# Data_IO.net
KiCad netlist of a schematic drawn in Altium Designer
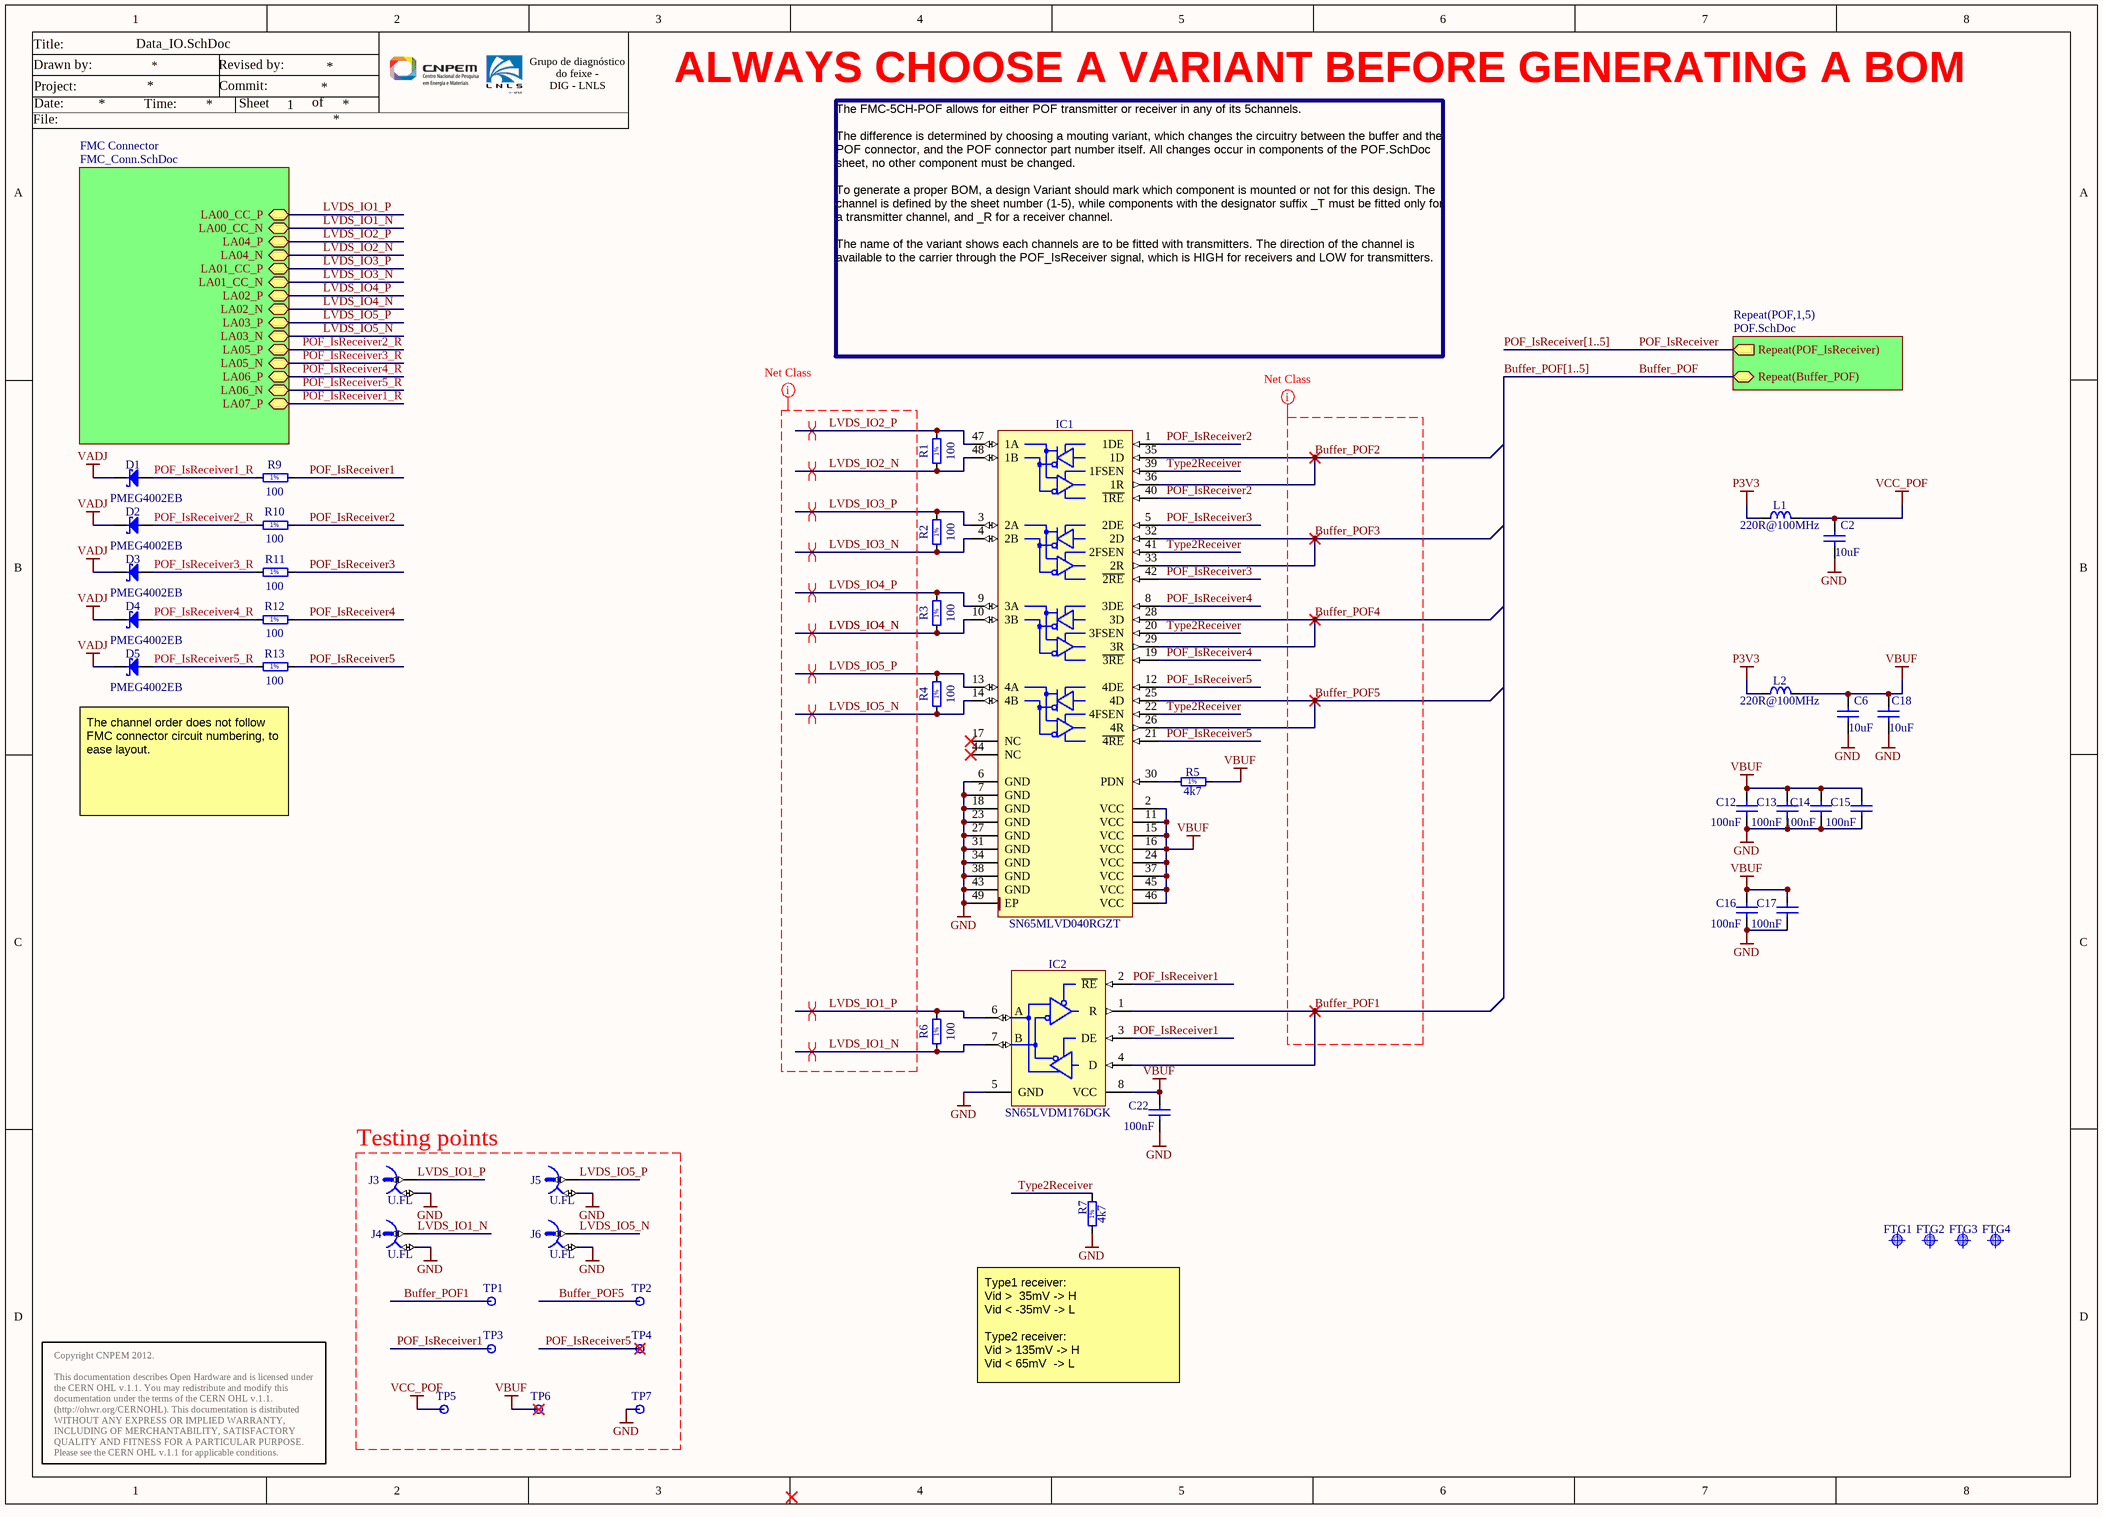
[diagram p0: Data_IO.SchDoc]

(export (version "E")
  (design (tool "Eeschema 10.0.6"))
  (components
    (comp (ref "C2")
      (value "10uF")
      (footprint "CAPC2012X135N")
      (description "Non-polarised capacitor")
      (fields
        (field (name "PART NUMBER") "CC0805_10UF_10V_10%_X7R")
        (field (name "VOLTAGE") "10V")
        (field (name "AUTHOR") "CERN DEM JLC")
      )
      (libsource (lib "Capacitors") (part "Capacitor - non polarized"))
    )
    (comp (ref "C6")
      (value "10uF")
      (footprint "CAPC2012X135N")
      (description "Non-polarised capacitor")
      (fields
        (field (name "PART NUMBER") "CC0805_10UF_10V_10%_X7R")
        (field (name "VOLTAGE") "10V")
        (field (name "AUTHOR") "CERN DEM JLC")
      )
      (libsource (lib "Capacitors") (part "Capacitor - non polarized"))
    )
    (comp (ref "C12")
      (value "100nF")
      (footprint "CAPC1005X55N")
      (description "Non-polarised capacitor")
      (fields
        (field (name "PART NUMBER") "CC0402_100NF_16V_10%_X5R")
        (field (name "VOLTAGE") "16V")
        (field (name "AUTHOR") "CERN DEM JLC")
      )
      (libsource (lib "Capacitors") (part "Capacitor - non polarized"))
    )
    (comp (ref "C13")
      (value "100nF")
      (footprint "CAPC1005X55N")
      (description "Non-polarised capacitor")
      (fields
        (field (name "PART NUMBER") "CC0402_100NF_16V_10%_X5R")
        (field (name "VOLTAGE") "16V")
        (field (name "AUTHOR") "CERN DEM JLC")
      )
      (libsource (lib "Capacitors") (part "Capacitor - non polarized"))
    )
    (comp (ref "C14")
      (value "100nF")
      (footprint "CAPC1005X55N")
      (description "Non-polarised capacitor")
      (fields
        (field (name "PART NUMBER") "CC0402_100NF_16V_10%_X5R")
        (field (name "VOLTAGE") "16V")
        (field (name "AUTHOR") "CERN DEM JLC")
      )
      (libsource (lib "Capacitors") (part "Capacitor - non polarized"))
    )
    (comp (ref "C15")
      (value "100nF")
      (footprint "CAPC1005X55N")
      (description "Non-polarised capacitor")
      (fields
        (field (name "PART NUMBER") "CC0402_100NF_16V_10%_X5R")
        (field (name "VOLTAGE") "16V")
        (field (name "AUTHOR") "CERN DEM JLC")
      )
      (libsource (lib "Capacitors") (part "Capacitor - non polarized"))
    )
    (comp (ref "C16")
      (value "100nF")
      (footprint "CAPC1005X55N")
      (description "Non-polarised capacitor")
      (fields
        (field (name "PART NUMBER") "CC0402_100NF_16V_10%_X5R")
        (field (name "VOLTAGE") "16V")
        (field (name "AUTHOR") "CERN DEM JLC")
      )
      (libsource (lib "Capacitors") (part "Capacitor - non polarized"))
    )
    (comp (ref "C17")
      (value "100nF")
      (footprint "CAPC1005X55N")
      (description "Non-polarised capacitor")
      (fields
        (field (name "PART NUMBER") "CC0402_100NF_16V_10%_X5R")
        (field (name "VOLTAGE") "16V")
        (field (name "AUTHOR") "CERN DEM JLC")
      )
      (libsource (lib "Capacitors") (part "Capacitor - non polarized"))
    )
    (comp (ref "C18")
      (value "10uF")
      (footprint "CAPC2012X135N")
      (description "Non-polarised capacitor")
      (fields
        (field (name "PART NUMBER") "CC0805_10UF_10V_10%_X7R")
        (field (name "VOLTAGE") "10V")
        (field (name "AUTHOR") "CERN DEM JLC")
      )
      (libsource (lib "Capacitors") (part "Capacitor - non polarized"))
    )
    (comp (ref "C22")
      (value "100nF")
      (footprint "CAPC1005X55N")
      (description "Non-polarised capacitor")
      (fields
        (field (name "PART NUMBER") "CC0402_100NF_16V_10%_X5R")
        (field (name "VOLTAGE") "16V")
        (field (name "AUTHOR") "CERN DEM JLC")
      )
      (libsource (lib "Capacitors") (part "Capacitor - non polarized"))
    )
    (comp (ref "D1")
      (value "PMEG4002EB")
      (footprint "SODFL1608X65N")
      (description "Schottky Diode")
      (fields
        (field (name "VOLTAGE") "40V")
        (field (name "POWER") "200mA")
        (field (name "AUTHOR") "CERN DEM JMW")
      )
      (libsource (lib "ICs And Semiconductors") (part "Diode Schottky"))
    )
    (comp (ref "D2")
      (value "PMEG4002EB")
      (footprint "SODFL1608X65N")
      (description "Schottky Diode")
      (fields
        (field (name "VOLTAGE") "40V")
        (field (name "POWER") "200mA")
        (field (name "AUTHOR") "CERN DEM JMW")
      )
      (libsource (lib "ICs And Semiconductors") (part "Diode Schottky"))
    )
    (comp (ref "D3")
      (value "PMEG4002EB")
      (footprint "SODFL1608X65N")
      (description "Schottky Diode")
      (fields
        (field (name "VOLTAGE") "40V")
        (field (name "POWER") "200mA")
        (field (name "AUTHOR") "CERN DEM JMW")
      )
      (libsource (lib "ICs And Semiconductors") (part "Diode Schottky"))
    )
    (comp (ref "D4")
      (value "PMEG4002EB")
      (footprint "SODFL1608X65N")
      (description "Schottky Diode")
      (fields
        (field (name "VOLTAGE") "40V")
        (field (name "POWER") "200mA")
        (field (name "AUTHOR") "CERN DEM JMW")
      )
      (libsource (lib "ICs And Semiconductors") (part "Diode Schottky"))
    )
    (comp (ref "D5")
      (value "PMEG4002EB")
      (footprint "SODFL1608X65N")
      (description "Schottky Diode")
      (fields
        (field (name "VOLTAGE") "40V")
        (field (name "POWER") "200mA")
        (field (name "AUTHOR") "CERN DEM JMW")
      )
      (libsource (lib "ICs And Semiconductors") (part "Diode Schottky"))
    )
    (comp (ref "FTG1")
      (value "Use only in PCB")
      (footprint "FIDUCIAL_TOP_S100-200")
      (description "Fiducial Target")
      (fields (field (name "PART NUMBER") "FIDUCIAL_TARGET_S100-200") (field (name "AUTHOR") "CERN DEM JLC"))
      (libsource (lib "Eletro-mechanical") (part "Fiducial Target"))
    )
    (comp (ref "FTG2")
      (value "Use only in PCB")
      (footprint "FIDUCIAL_TOP_S100-200")
      (description "Fiducial Target")
      (fields (field (name "PART NUMBER") "FIDUCIAL_TARGET_S100-200") (field (name "AUTHOR") "CERN DEM JLC"))
      (libsource (lib "Eletro-mechanical") (part "Fiducial Target"))
    )
    (comp (ref "FTG3")
      (value "Use only in PCB")
      (footprint "FIDUCIAL_TOP_S100-200")
      (description "Fiducial Target")
      (fields (field (name "PART NUMBER") "FIDUCIAL_TARGET_S100-200") (field (name "AUTHOR") "CERN DEM JLC"))
      (libsource (lib "Eletro-mechanical") (part "Fiducial Target"))
    )
    (comp (ref "FTG4")
      (value "Use only in PCB")
      (footprint "FIDUCIAL_TOP_S100-200")
      (description "Fiducial Target")
      (fields (field (name "PART NUMBER") "FIDUCIAL_TARGET_S100-200") (field (name "AUTHOR") "CERN DEM JLC"))
      (libsource (lib "Eletro-mechanical") (part "Fiducial Target"))
    )
    (comp (ref "IC1")
      (value "SN65MLVD040RGZT")
      (footprint "QFN50P700X700X100-49N-S420")
      (description "4-Channel Half-Duplex M-LVDS Line Transceiver")
      (fields (field (name "MANUFACTURER") "TEXAS INSTRUMENTS") (field (name "AUTHOR") "CERN DEM JLC"))
      (libsource (lib "ICs And Semiconductors") (part "SN65MLVD040"))
    )
    (comp (ref "IC2")
      (value "SN65LVDM176DGK")
      (footprint "SOP65P490X110-8N")
      (description "Half-Duplex LVDM Transceiver")
      (fields (field (name "MANUFACTURER") "TEXAS INSTRUMENTS") (field (name "AUTHOR") "CERN DEM JLC"))
      (libsource (lib "ICs And Semiconductors") (part "SN65LVDM176"))
    )
    (comp (ref "J3")
      (value "U.FL")
      (footprint "HIROSE_U.FL-R-SMT-1(10)")
      (fields
        (field (name "PART NUMBER") "HIROSE_U.FL-R-SMT-1(10)")
        (field (name "MANUFACTURER") "HIROSE (HRS)")
        (field (name "MANUFACTURER PART NUMBER") "U.FL-R-SMT-1(10)")
        (field (name "AUTHOR") "CERN DEM JLC")
      )
      (libsource (lib "Connectors") (part "Coax_1Male_1Shield"))
    )
    (comp (ref "J4")
      (value "U.FL")
      (footprint "HIROSE_U.FL-R-SMT-1(10)")
      (fields
        (field (name "PART NUMBER") "HIROSE_U.FL-R-SMT-1(10)")
        (field (name "MANUFACTURER") "HIROSE (HRS)")
        (field (name "MANUFACTURER PART NUMBER") "U.FL-R-SMT-1(10)")
        (field (name "AUTHOR") "CERN DEM JLC")
      )
      (libsource (lib "Connectors") (part "Coax_1Male_1Shield"))
    )
    (comp (ref "J5")
      (value "U.FL")
      (footprint "HIROSE_U.FL-R-SMT-1(10)")
      (fields
        (field (name "PART NUMBER") "HIROSE_U.FL-R-SMT-1(10)")
        (field (name "MANUFACTURER") "HIROSE (HRS)")
        (field (name "MANUFACTURER PART NUMBER") "U.FL-R-SMT-1(10)")
        (field (name "AUTHOR") "CERN DEM JLC")
      )
      (libsource (lib "Connectors") (part "Coax_1Male_1Shield"))
    )
    (comp (ref "J6")
      (value "U.FL")
      (footprint "HIROSE_U.FL-R-SMT-1(10)")
      (fields
        (field (name "PART NUMBER") "HIROSE_U.FL-R-SMT-1(10)")
        (field (name "MANUFACTURER") "HIROSE (HRS)")
        (field (name "MANUFACTURER PART NUMBER") "U.FL-R-SMT-1(10)")
        (field (name "AUTHOR") "CERN DEM JLC")
      )
      (libsource (lib "Connectors") (part "Coax_1Male_1Shield"))
    )
    (comp (ref "L1")
      (value "220R@100MHz")
      (footprint "INDC2012X105N")
      (description "Inductor")
      (fields
        (field (name "PART NUMBER") "IND0805_MURATA_BLM21PG221SN1D")
        (field (name "POWER") "2A")
        (field (name "AUTHOR") "CERN DEM JLC")
      )
      (libsource (lib "Inductors & Transformers") (part "Inductor"))
    )
    (comp (ref "L2")
      (value "220R@100MHz")
      (footprint "INDC2012X105N")
      (description "Inductor")
      (fields
        (field (name "PART NUMBER") "IND0805_MURATA_BLM21PG221SN1D")
        (field (name "POWER") "2A")
        (field (name "AUTHOR") "CERN DEM JLC")
      )
      (libsource (lib "Inductors & Transformers") (part "Inductor"))
    )
    (comp (ref "R1")
      (value "100")
      (footprint "RESC1005X40N")
      (description "Resistor - 1%")
      (fields
        (field (name "PART NUMBER") "R0402_100R_1%_0.0625W_100PPM")
        (field (name "POWER") "0.0625W")
        (field (name "AUTHOR") "CERN DEM JLC")
      )
      (libsource (lib "Resistors") (part "Resistor - 1%"))
    )
    (comp (ref "R2")
      (value "100")
      (footprint "RESC1005X40N")
      (description "Resistor - 1%")
      (fields
        (field (name "PART NUMBER") "R0402_100R_1%_0.0625W_100PPM")
        (field (name "POWER") "0.0625W")
        (field (name "AUTHOR") "CERN DEM JLC")
      )
      (libsource (lib "Resistors") (part "Resistor - 1%"))
    )
    (comp (ref "R3")
      (value "100")
      (footprint "RESC1005X40N")
      (description "Resistor - 1%")
      (fields
        (field (name "PART NUMBER") "R0402_100R_1%_0.0625W_100PPM")
        (field (name "POWER") "0.0625W")
        (field (name "AUTHOR") "CERN DEM JLC")
      )
      (libsource (lib "Resistors") (part "Resistor - 1%"))
    )
    (comp (ref "R4")
      (value "100")
      (footprint "RESC1005X40N")
      (description "Resistor - 1%")
      (fields
        (field (name "PART NUMBER") "R0402_100R_1%_0.0625W_100PPM")
        (field (name "POWER") "0.0625W")
        (field (name "AUTHOR") "CERN DEM JLC")
      )
      (libsource (lib "Resistors") (part "Resistor - 1%"))
    )
    (comp (ref "R5")
      (value "4k7")
      (footprint "RESC1005X40N")
      (description "Resistor - 1%")
      (fields
        (field (name "PART NUMBER") "R0402_4K7_1%_0.0625W_100PPM")
        (field (name "POWER") "0.0625W")
        (field (name "AUTHOR") "CERN DEM JLC")
      )
      (libsource (lib "Resistors") (part "Resistor - 1%"))
    )
    (comp (ref "R6")
      (value "100")
      (footprint "RESC1005X40N")
      (description "Resistor - 1%")
      (fields
        (field (name "PART NUMBER") "R0402_100R_1%_0.0625W_100PPM")
        (field (name "POWER") "0.0625W")
        (field (name "AUTHOR") "CERN DEM JLC")
      )
      (libsource (lib "Resistors") (part "Resistor - 1%"))
    )
    (comp (ref "R7")
      (value "4k7")
      (footprint "RESC1005X40N")
      (description "Resistor - 1%")
      (fields
        (field (name "PART NUMBER") "R0402_4K7_1%_0.0625W_100PPM")
        (field (name "POWER") "0.0625W")
        (field (name "AUTHOR") "CERN DEM JLC")
      )
      (libsource (lib "Resistors") (part "Resistor - 1%"))
    )
    (comp (ref "R9")
      (value "100")
      (footprint "RESC1005X40N")
      (description "Resistor - 1%")
      (fields
        (field (name "PART NUMBER") "R0402_100R_1%_0.0625W_100PPM")
        (field (name "POWER") "0.0625W")
        (field (name "AUTHOR") "CERN DEM JLC")
      )
      (libsource (lib "Resistors") (part "Resistor - 1%"))
    )
    (comp (ref "R10")
      (value "100")
      (footprint "RESC1005X40N")
      (description "Resistor - 1%")
      (fields
        (field (name "PART NUMBER") "R0402_100R_1%_0.0625W_100PPM")
        (field (name "POWER") "0.0625W")
        (field (name "AUTHOR") "CERN DEM JLC")
      )
      (libsource (lib "Resistors") (part "Resistor - 1%"))
    )
    (comp (ref "R11")
      (value "100")
      (footprint "RESC1005X40N")
      (description "Resistor - 1%")
      (fields
        (field (name "PART NUMBER") "R0402_100R_1%_0.0625W_100PPM")
        (field (name "POWER") "0.0625W")
        (field (name "AUTHOR") "CERN DEM JLC")
      )
      (libsource (lib "Resistors") (part "Resistor - 1%"))
    )
    (comp (ref "R12")
      (value "100")
      (footprint "RESC1005X40N")
      (description "Resistor - 1%")
      (fields
        (field (name "PART NUMBER") "R0402_100R_1%_0.0625W_100PPM")
        (field (name "POWER") "0.0625W")
        (field (name "AUTHOR") "CERN DEM JLC")
      )
      (libsource (lib "Resistors") (part "Resistor - 1%"))
    )
    (comp (ref "R13")
      (value "100")
      (footprint "RESC1005X40N")
      (description "Resistor - 1%")
      (fields
        (field (name "PART NUMBER") "R0402_100R_1%_0.0625W_100PPM")
        (field (name "POWER") "0.0625W")
        (field (name "AUTHOR") "CERN DEM JLC")
      )
      (libsource (lib "Resistors") (part "Resistor - 1%"))
    )
    (comp (ref "TP1")
      (value "Plated Hole")
      (footprint "c300h160")
      (description "Single Terminal Socket")
      (fields (field (name "PART NUMBER") "PLATED_HOLE1.6_PAD3.0") (field (name "AUTHOR") "CERN DEM JMW"))
      (libsource (lib "Eletro-mechanical") (part "Single Terminal Socket"))
    )
    (comp (ref "TP2")
      (value "Plated Hole")
      (footprint "c300h160")
      (description "Single Terminal Socket")
      (fields (field (name "PART NUMBER") "PLATED_HOLE1.6_PAD3.0") (field (name "AUTHOR") "CERN DEM JMW"))
      (libsource (lib "Eletro-mechanical") (part "Single Terminal Socket"))
    )
    (comp (ref "TP3")
      (value "Plated Hole")
      (footprint "c300h160")
      (description "Single Terminal Socket")
      (fields (field (name "PART NUMBER") "PLATED_HOLE1.6_PAD3.0") (field (name "AUTHOR") "CERN DEM JMW"))
      (libsource (lib "Eletro-mechanical") (part "Single Terminal Socket"))
    )
    (comp (ref "TP4")
      (value "Plated Hole")
      (footprint "c300h160")
      (description "Single Terminal Socket")
      (fields (field (name "PART NUMBER") "PLATED_HOLE1.6_PAD3.0") (field (name "AUTHOR") "CERN DEM JMW"))
      (libsource (lib "Eletro-mechanical") (part "Single Terminal Socket"))
    )
    (comp (ref "TP5")
      (value "Plated Hole")
      (footprint "c300h160")
      (description "Single Terminal Socket")
      (fields (field (name "PART NUMBER") "PLATED_HOLE1.6_PAD3.0") (field (name "AUTHOR") "CERN DEM JMW"))
      (libsource (lib "Eletro-mechanical") (part "Single Terminal Socket"))
    )
    (comp (ref "TP6")
      (value "Plated Hole")
      (footprint "c300h160")
      (description "Single Terminal Socket")
      (fields (field (name "PART NUMBER") "PLATED_HOLE1.6_PAD3.0") (field (name "AUTHOR") "CERN DEM JMW"))
      (libsource (lib "Eletro-mechanical") (part "Single Terminal Socket"))
    )
    (comp (ref "TP7")
      (value "Plated Hole")
      (footprint "c300h160")
      (description "Single Terminal Socket")
      (fields (field (name "PART NUMBER") "PLATED_HOLE1.6_PAD3.0") (field (name "AUTHOR") "CERN DEM JMW"))
      (libsource (lib "Eletro-mechanical") (part "Single Terminal Socket"))
    )
  )
  (nets
    (net (code "2") (name "/Buffer_POF1") (class "Default")
      (node (ref "IC2") (pin "1") (pinfunction "R_1") (pintype "output"))
      (node (ref "IC2") (pin "4") (pinfunction "D_4") (pintype "input"))
      (node (ref "TP1") (pin "1") (pinfunction "1_1") (pintype "bidirectional"))
    )
    (net (code "3") (name "/Buffer_POF2") (class "Default")
      (node (ref "IC1") (pin "35") (pinfunction "1D_35") (pintype "input"))
      (node (ref "IC1") (pin "36") (pinfunction "1R_36") (pintype "output"))
    )
    (net (code "4") (name "/Buffer_POF3") (class "Default")
      (node (ref "IC1") (pin "32") (pinfunction "2D_32") (pintype "input"))
      (node (ref "IC1") (pin "33") (pinfunction "2R_33") (pintype "output"))
    )
    (net (code "5") (name "/Buffer_POF4") (class "Default")
      (node (ref "IC1") (pin "28") (pinfunction "3D_28") (pintype "input"))
      (node (ref "IC1") (pin "29") (pinfunction "3R_29") (pintype "output"))
    )
    (net (code "6") (name "/Buffer_POF5") (class "Default")
      (node (ref "IC1") (pin "25") (pinfunction "4D_25") (pintype "input"))
      (node (ref "IC1") (pin "26") (pinfunction "4R_26") (pintype "output"))
      (node (ref "TP2") (pin "1") (pinfunction "1_1") (pintype "bidirectional"))
    )
    (net (code "8") (name "/LVDS_IO1_N") (class "Default")
      (node (ref "IC2") (pin "7") (pinfunction "B_7") (pintype "bidirectional"))
      (node (ref "J4") (pin "1") (pinfunction "1_1") (pintype "bidirectional"))
      (node (ref "R6") (pin "1") (pinfunction "1_1") (pintype "passive"))
    )
    (net (code "9") (name "/LVDS_IO1_P") (class "Default")
      (node (ref "IC2") (pin "6") (pinfunction "A_6") (pintype "bidirectional"))
      (node (ref "J3") (pin "1") (pinfunction "1_1") (pintype "bidirectional"))
      (node (ref "R6") (pin "2") (pinfunction "2_2") (pintype "passive"))
    )
    (net (code "10") (name "/LVDS_IO2_N") (class "Default")
      (node (ref "IC1") (pin "48") (pinfunction "1B_48") (pintype "bidirectional"))
      (node (ref "R1") (pin "1") (pinfunction "1_1") (pintype "passive"))
    )
    (net (code "11") (name "/LVDS_IO2_P") (class "Default")
      (node (ref "IC1") (pin "47") (pinfunction "1A_47") (pintype "bidirectional"))
      (node (ref "R1") (pin "2") (pinfunction "2_2") (pintype "passive"))
    )
    (net (code "12") (name "/LVDS_IO3_N") (class "Default")
      (node (ref "IC1") (pin "4") (pinfunction "2B_4") (pintype "bidirectional"))
      (node (ref "R2") (pin "1") (pinfunction "1_1") (pintype "passive"))
    )
    (net (code "13") (name "/LVDS_IO3_P") (class "Default")
      (node (ref "IC1") (pin "3") (pinfunction "2A_3") (pintype "bidirectional"))
      (node (ref "R2") (pin "2") (pinfunction "2_2") (pintype "passive"))
    )
    (net (code "14") (name "/LVDS_IO4_N") (class "Default")
      (node (ref "IC1") (pin "10") (pinfunction "3B_10") (pintype "bidirectional"))
      (node (ref "R3") (pin "1") (pinfunction "1_1") (pintype "passive"))
    )
    (net (code "15") (name "/LVDS_IO4_P") (class "Default")
      (node (ref "IC1") (pin "9") (pinfunction "3A_9") (pintype "bidirectional"))
      (node (ref "R3") (pin "2") (pinfunction "2_2") (pintype "passive"))
    )
    (net (code "16") (name "/LVDS_IO5_N") (class "Default")
      (node (ref "IC1") (pin "14") (pinfunction "4B_14") (pintype "bidirectional"))
      (node (ref "J6") (pin "1") (pinfunction "1_1") (pintype "bidirectional"))
      (node (ref "R4") (pin "1") (pinfunction "1_1") (pintype "passive"))
    )
    (net (code "17") (name "/LVDS_IO5_P") (class "Default")
      (node (ref "IC1") (pin "13") (pinfunction "4A_13") (pintype "bidirectional"))
      (node (ref "J5") (pin "1") (pinfunction "1_1") (pintype "bidirectional"))
      (node (ref "R4") (pin "2") (pinfunction "2_2") (pintype "passive"))
    )
    (net (code "19") (name "/POF_IsReceiver1") (class "Default")
      (node (ref "IC2") (pin "2") (pinfunction "~{RE}_2") (pintype "input"))
      (node (ref "IC2") (pin "3") (pinfunction "DE_3") (pintype "input"))
      (node (ref "R9") (pin "2") (pinfunction "2_2") (pintype "passive"))
      (node (ref "TP3") (pin "1") (pinfunction "1_1") (pintype "bidirectional"))
    )
    (net (code "20") (name "/POF_IsReceiver1_R") (class "Default")
      (node (ref "D1") (pin "2") (pinfunction "A_2") (pintype "passive"))
      (node (ref "R9") (pin "1") (pinfunction "1_1") (pintype "passive"))
    )
    (net (code "21") (name "/POF_IsReceiver2") (class "Default")
      (node (ref "IC1") (pin "1") (pinfunction "1DE_1") (pintype "input"))
      (node (ref "IC1") (pin "40") (pinfunction "~{1RE}_40") (pintype "input"))
      (node (ref "R10") (pin "2") (pinfunction "2_2") (pintype "passive"))
    )
    (net (code "22") (name "/POF_IsReceiver2_R") (class "Default")
      (node (ref "D2") (pin "2") (pinfunction "A_2") (pintype "passive"))
      (node (ref "R10") (pin "1") (pinfunction "1_1") (pintype "passive"))
    )
    (net (code "23") (name "/POF_IsReceiver3") (class "Default")
      (node (ref "IC1") (pin "42") (pinfunction "~{2RE}_42") (pintype "input"))
      (node (ref "IC1") (pin "5") (pinfunction "2DE_5") (pintype "input"))
      (node (ref "R11") (pin "2") (pinfunction "2_2") (pintype "passive"))
    )
    (net (code "24") (name "/POF_IsReceiver3_R") (class "Default")
      (node (ref "D3") (pin "2") (pinfunction "A_2") (pintype "passive"))
      (node (ref "R11") (pin "1") (pinfunction "1_1") (pintype "passive"))
    )
    (net (code "25") (name "/POF_IsReceiver4") (class "Default")
      (node (ref "IC1") (pin "19") (pinfunction "~{3RE}_19") (pintype "input"))
      (node (ref "IC1") (pin "8") (pinfunction "3DE_8") (pintype "input"))
      (node (ref "R12") (pin "2") (pinfunction "2_2") (pintype "passive"))
    )
    (net (code "26") (name "/POF_IsReceiver4_R") (class "Default")
      (node (ref "D4") (pin "2") (pinfunction "A_2") (pintype "passive"))
      (node (ref "R12") (pin "1") (pinfunction "1_1") (pintype "passive"))
    )
    (net (code "27") (name "/POF_IsReceiver5") (class "Default")
      (node (ref "IC1") (pin "12") (pinfunction "4DE_12") (pintype "input"))
      (node (ref "IC1") (pin "21") (pinfunction "~{4RE}_21") (pintype "input"))
      (node (ref "R13") (pin "2") (pinfunction "2_2") (pintype "passive"))
      (node (ref "TP4") (pin "1") (pinfunction "1_1") (pintype "bidirectional"))
    )
    (net (code "28") (name "/POF_IsReceiver5_R") (class "Default")
      (node (ref "D5") (pin "2") (pinfunction "A_2") (pintype "passive"))
      (node (ref "R13") (pin "1") (pinfunction "1_1") (pintype "passive"))
    )
    (net (code "30") (name "/Type2Receiver") (class "Default")
      (node (ref "IC1") (pin "20") (pinfunction "3FSEN_20") (pintype "input"))
      (node (ref "IC1") (pin "22") (pinfunction "4FSEN_22") (pintype "input"))
      (node (ref "IC1") (pin "39") (pinfunction "1FSEN_39") (pintype "input"))
      (node (ref "IC1") (pin "41") (pinfunction "2FSEN_41") (pintype "input"))
      (node (ref "R7") (pin "2") (pinfunction "2_2") (pintype "passive"))
    )
    (net (code "31") (name "GND") (class "Default")
      (node (ref "C12") (pin "1") (pinfunction "1_1") (pintype "passive"))
      (node (ref "C13") (pin "1") (pinfunction "1_1") (pintype "passive"))
      (node (ref "C14") (pin "1") (pinfunction "1_1") (pintype "passive"))
      (node (ref "C15") (pin "1") (pinfunction "1_1") (pintype "passive"))
      (node (ref "C16") (pin "1") (pinfunction "1_1") (pintype "passive"))
      (node (ref "C17") (pin "1") (pinfunction "1_1") (pintype "passive"))
      (node (ref "C18") (pin "1") (pinfunction "1_1") (pintype "passive"))
      (node (ref "C2") (pin "1") (pinfunction "1_1") (pintype "passive"))
      (node (ref "C22") (pin "1") (pinfunction "1_1") (pintype "passive"))
      (node (ref "C6") (pin "1") (pinfunction "1_1") (pintype "passive"))
      (node (ref "IC1") (pin "18") (pinfunction "GND_18") (pintype "power_in"))
      (node (ref "IC1") (pin "23") (pinfunction "GND_23") (pintype "power_in"))
      (node (ref "IC1") (pin "27") (pinfunction "GND_27") (pintype "power_in"))
      (node (ref "IC1") (pin "31") (pinfunction "GND_31") (pintype "power_in"))
      (node (ref "IC1") (pin "34") (pinfunction "GND_34") (pintype "power_in"))
      (node (ref "IC1") (pin "38") (pinfunction "GND_38") (pintype "power_in"))
      (node (ref "IC1") (pin "43") (pinfunction "GND_43") (pintype "power_in"))
      (node (ref "IC1") (pin "49") (pinfunction "EP_49") (pintype "power_in"))
      (node (ref "IC1") (pin "6") (pinfunction "GND_6") (pintype "power_in"))
      (node (ref "IC1") (pin "7") (pinfunction "GND_7") (pintype "power_in"))
      (node (ref "IC2") (pin "5") (pinfunction "GND_5") (pintype "power_in"))
      (node (ref "J3") (pin "2") (pinfunction "2_2") (pintype "bidirectional"))
      (node (ref "J4") (pin "2") (pinfunction "2_2") (pintype "bidirectional"))
      (node (ref "J5") (pin "2") (pinfunction "2_2") (pintype "bidirectional"))
      (node (ref "J6") (pin "2") (pinfunction "2_2") (pintype "bidirectional"))
      (node (ref "R7") (pin "1") (pinfunction "1_1") (pintype "passive"))
      (node (ref "TP7") (pin "1") (pinfunction "1_1") (pintype "bidirectional"))
    )
    (net (code "32") (name "Net-(IC1-PDN)") (class "Default")
      (node (ref "IC1") (pin "30") (pinfunction "PDN_30") (pintype "input"))
      (node (ref "R5") (pin "1") (pinfunction "1_1") (pintype "passive"))
    )
    (net (code "33") (name "P3V3") (class "Default")
      (node (ref "L1") (pin "1") (pinfunction "1_1") (pintype "passive"))
      (node (ref "L2") (pin "1") (pinfunction "1_1") (pintype "passive"))
    )
    (net (code "34") (name "VADJ") (class "Default")
      (node (ref "D1") (pin "1") (pinfunction "C_1") (pintype "passive"))
      (node (ref "D2") (pin "1") (pinfunction "C_1") (pintype "passive"))
      (node (ref "D3") (pin "1") (pinfunction "C_1") (pintype "passive"))
      (node (ref "D4") (pin "1") (pinfunction "C_1") (pintype "passive"))
      (node (ref "D5") (pin "1") (pinfunction "C_1") (pintype "passive"))
    )
    (net (code "35") (name "VBUF") (class "Default")
      (node (ref "C12") (pin "2") (pinfunction "2_2") (pintype "passive"))
      (node (ref "C13") (pin "2") (pinfunction "2_2") (pintype "passive"))
      (node (ref "C14") (pin "2") (pinfunction "2_2") (pintype "passive"))
      (node (ref "C15") (pin "2") (pinfunction "2_2") (pintype "passive"))
      (node (ref "C16") (pin "2") (pinfunction "2_2") (pintype "passive"))
      (node (ref "C17") (pin "2") (pinfunction "2_2") (pintype "passive"))
      (node (ref "C18") (pin "2") (pinfunction "2_2") (pintype "passive"))
      (node (ref "C22") (pin "2") (pinfunction "2_2") (pintype "passive"))
      (node (ref "C6") (pin "2") (pinfunction "2_2") (pintype "passive"))
      (node (ref "IC1") (pin "11") (pinfunction "VCC_11") (pintype "power_in"))
      (node (ref "IC1") (pin "15") (pinfunction "VCC_15") (pintype "power_in"))
      (node (ref "IC1") (pin "16") (pinfunction "VCC_16") (pintype "power_in"))
      (node (ref "IC1") (pin "2") (pinfunction "VCC_2") (pintype "power_in"))
      (node (ref "IC1") (pin "24") (pinfunction "VCC_24") (pintype "power_in"))
      (node (ref "IC1") (pin "37") (pinfunction "VCC_37") (pintype "power_in"))
      (node (ref "IC1") (pin "45") (pinfunction "VCC_45") (pintype "power_in"))
      (node (ref "IC1") (pin "46") (pinfunction "VCC_46") (pintype "power_in"))
      (node (ref "IC2") (pin "8") (pinfunction "VCC_8") (pintype "power_in"))
      (node (ref "L2") (pin "2") (pinfunction "2_2") (pintype "passive"))
      (node (ref "R5") (pin "2") (pinfunction "2_2") (pintype "passive"))
      (node (ref "TP6") (pin "1") (pinfunction "1_1") (pintype "bidirectional"))
    )
    (net (code "36") (name "VCC_POF") (class "Default")
      (node (ref "C2") (pin "2") (pinfunction "2_2") (pintype "passive"))
      (node (ref "L1") (pin "2") (pinfunction "2_2") (pintype "passive"))
      (node (ref "TP5") (pin "1") (pinfunction "1_1") (pintype "bidirectional"))
    )
    (net (code "37") (name "unconnected-(IC1-NC-Pad17)") (class "Default")
      (node (ref "IC1") (pin "17") (pinfunction "NC_17") (pintype "passive+no_connect"))
    )
    (net (code "38") (name "unconnected-(IC1-NC-Pad44)") (class "Default")
      (node (ref "IC1") (pin "44") (pinfunction "NC_44") (pintype "passive+no_connect"))
    )
  )
)
